# KW_LCD.net
KiCad netlist of a schematic drawn in EAGLE
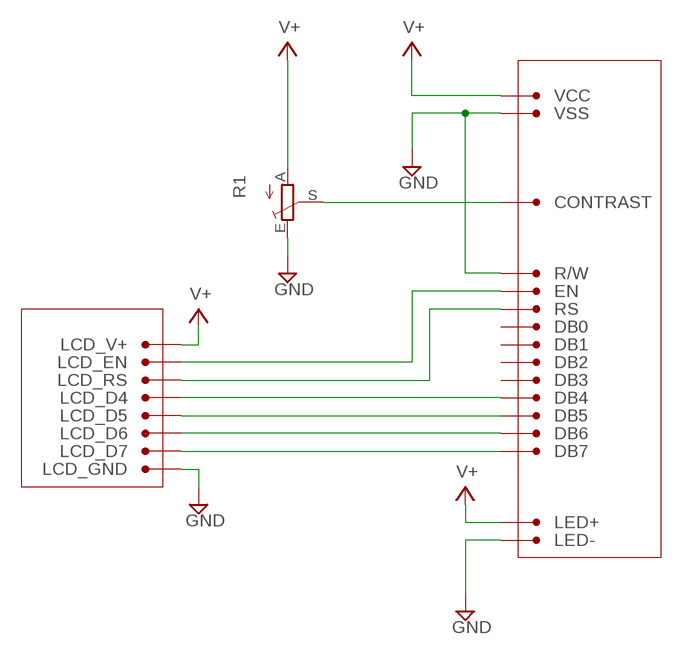
[diagram p0: schematic, sheet 1]

(export (version "E")
  (design (tool "Eeschema 10.0.6"))
  (components
    (comp (ref "CONTRAST")
      (value "3")
      (footprint "eagle-import:CONN")
      (libsource (lib "eagle-import") (part "CONN"))
    )
    (comp (ref "DB0")
      (value "7")
      (footprint "eagle-import:CONN")
      (libsource (lib "eagle-import") (part "CONN"))
    )
    (comp (ref "DB1")
      (value "8")
      (footprint "eagle-import:CONN")
      (libsource (lib "eagle-import") (part "CONN"))
    )
    (comp (ref "DB2")
      (value "9")
      (footprint "eagle-import:CONN")
      (libsource (lib "eagle-import") (part "CONN"))
    )
    (comp (ref "DB3")
      (value "10")
      (footprint "eagle-import:CONN")
      (libsource (lib "eagle-import") (part "CONN"))
    )
    (comp (ref "DB4")
      (value "11")
      (footprint "eagle-import:CONN")
      (libsource (lib "eagle-import") (part "CONN"))
    )
    (comp (ref "DB5")
      (value "12")
      (footprint "eagle-import:CONN")
      (libsource (lib "eagle-import") (part "CONN"))
    )
    (comp (ref "DB6")
      (value "13")
      (footprint "eagle-import:CONN")
      (libsource (lib "eagle-import") (part "CONN"))
    )
    (comp (ref "DB7")
      (value "14")
      (footprint "eagle-import:CONN")
      (libsource (lib "eagle-import") (part "CONN"))
    )
    (comp (ref "EN")
      (value "6")
      (footprint "eagle-import:CONN")
      (libsource (lib "eagle-import") (part "CONN"))
    )
    (comp (ref "LCD_D4")
      (value "14")
      (footprint "eagle-import:CONN")
      (libsource (lib "eagle-import") (part "CONN"))
    )
    (comp (ref "LCD_D5")
      (value "14")
      (footprint "eagle-import:CONN")
      (libsource (lib "eagle-import") (part "CONN"))
    )
    (comp (ref "LCD_D6")
      (value "14")
      (footprint "eagle-import:CONN")
      (libsource (lib "eagle-import") (part "CONN"))
    )
    (comp (ref "LCD_D7")
      (value "14")
      (footprint "eagle-import:CONN")
      (libsource (lib "eagle-import") (part "CONN"))
    )
    (comp (ref "LCD_EN")
      (value "14")
      (footprint "eagle-import:CONN")
      (libsource (lib "eagle-import") (part "CONN"))
    )
    (comp (ref "LCD_GND")
      (value "14")
      (footprint "eagle-import:CONN")
      (libsource (lib "eagle-import") (part "CONN"))
    )
    (comp (ref "LCD_RS")
      (value "14")
      (footprint "eagle-import:CONN")
      (libsource (lib "eagle-import") (part "CONN"))
    )
    (comp (ref "LCD_V+")
      (value "14")
      (footprint "eagle-import:CONN")
      (libsource (lib "eagle-import") (part "CONN"))
    )
    (comp (ref "LED+")
      (value "16")
      (footprint "eagle-import:CONN")
      (libsource (lib "eagle-import") (part "CONN"))
    )
    (comp (ref "LED-")
      (value "15")
      (footprint "eagle-import:CONN")
      (libsource (lib "eagle-import") (part "CONN"))
    )
    (comp (ref "R/W")
      (value "5")
      (footprint "eagle-import:CONN")
      (libsource (lib "eagle-import") (part "CONN"))
    )
    (comp (ref "R1")
      (value "TRIM_EU-ECP10S")
      (footprint "eagle-import:ECP10S")
      (libsource (lib "eagle-import") (part "TRIM_EU-ECP10S"))
    )
    (comp (ref "RS")
      (value "4")
      (footprint "eagle-import:CONN")
      (libsource (lib "eagle-import") (part "CONN"))
    )
    (comp (ref "VCC")
      (value "2")
      (footprint "eagle-import:CONN")
      (libsource (lib "eagle-import") (part "CONN"))
    )
    (comp (ref "VSS")
      (value "1")
      (footprint "eagle-import:CONN")
      (libsource (lib "eagle-import") (part "CONN"))
    )
  )
  (nets
    (net (code "1") (name "GND") (class "Default")
      (node (ref "LCD_GND") (pin "P$1") (pinfunction "P$1_P$1") (pintype "bidirectional"))
      (node (ref "LED-") (pin "P$1") (pinfunction "P$1_P$1") (pintype "bidirectional"))
      (node (ref "R/W") (pin "P$1") (pinfunction "P$1_P$1") (pintype "bidirectional"))
      (node (ref "R1") (pin "E") (pinfunction "E_E") (pintype "passive"))
      (node (ref "VSS") (pin "P$1") (pinfunction "P$1_P$1") (pintype "bidirectional"))
    )
    (net (code "2") (name "Net-(CONTRAST-PadP$1)") (class "Default")
      (node (ref "CONTRAST") (pin "P$1") (pinfunction "P$1_P$1") (pintype "bidirectional"))
      (node (ref "R1") (pin "S") (pinfunction "S_S") (pintype "passive"))
    )
    (net (code "3") (name "Net-(DB4-PadP$1)") (class "Default")
      (node (ref "DB4") (pin "P$1") (pinfunction "P$1_P$1") (pintype "bidirectional"))
      (node (ref "LCD_D4") (pin "P$1") (pinfunction "P$1_P$1") (pintype "bidirectional"))
    )
    (net (code "4") (name "Net-(DB5-PadP$1)") (class "Default")
      (node (ref "DB5") (pin "P$1") (pinfunction "P$1_P$1") (pintype "bidirectional"))
      (node (ref "LCD_D5") (pin "P$1") (pinfunction "P$1_P$1") (pintype "bidirectional"))
    )
    (net (code "5") (name "Net-(DB6-PadP$1)") (class "Default")
      (node (ref "DB6") (pin "P$1") (pinfunction "P$1_P$1") (pintype "bidirectional"))
      (node (ref "LCD_D6") (pin "P$1") (pinfunction "P$1_P$1") (pintype "bidirectional"))
    )
    (net (code "6") (name "Net-(DB7-PadP$1)") (class "Default")
      (node (ref "DB7") (pin "P$1") (pinfunction "P$1_P$1") (pintype "bidirectional"))
      (node (ref "LCD_D7") (pin "P$1") (pinfunction "P$1_P$1") (pintype "bidirectional"))
    )
    (net (code "7") (name "Net-(EN-PadP$1)") (class "Default")
      (node (ref "EN") (pin "P$1") (pinfunction "P$1_P$1") (pintype "bidirectional"))
      (node (ref "LCD_EN") (pin "P$1") (pinfunction "P$1_P$1") (pintype "bidirectional"))
    )
    (net (code "8") (name "Net-(LCD_RS-PadP$1)") (class "Default")
      (node (ref "LCD_RS") (pin "P$1") (pinfunction "P$1_P$1") (pintype "bidirectional"))
      (node (ref "RS") (pin "P$1") (pinfunction "P$1_P$1") (pintype "bidirectional"))
    )
    (net (code "9") (name "V+") (class "Default")
      (node (ref "LCD_V+") (pin "P$1") (pinfunction "P$1_P$1") (pintype "bidirectional"))
      (node (ref "LED+") (pin "P$1") (pinfunction "P$1_P$1") (pintype "bidirectional"))
      (node (ref "R1") (pin "A") (pinfunction "A_A") (pintype "passive"))
      (node (ref "VCC") (pin "P$1") (pinfunction "P$1_P$1") (pintype "bidirectional"))
    )
    (net (code "10") (name "unconnected-(DB0-PadP$1)") (class "Default")
      (node (ref "DB0") (pin "P$1") (pinfunction "P$1_P$1") (pintype "bidirectional"))
    )
    (net (code "11") (name "unconnected-(DB1-PadP$1)") (class "Default")
      (node (ref "DB1") (pin "P$1") (pinfunction "P$1_P$1") (pintype "bidirectional"))
    )
    (net (code "12") (name "unconnected-(DB2-PadP$1)") (class "Default")
      (node (ref "DB2") (pin "P$1") (pinfunction "P$1_P$1") (pintype "bidirectional"))
    )
    (net (code "13") (name "unconnected-(DB3-PadP$1)") (class "Default")
      (node (ref "DB3") (pin "P$1") (pinfunction "P$1_P$1") (pintype "bidirectional"))
    )
  )
)
